# tick-display-mk-4.net
KiCad netlist of a schematic drawn in EAGLE
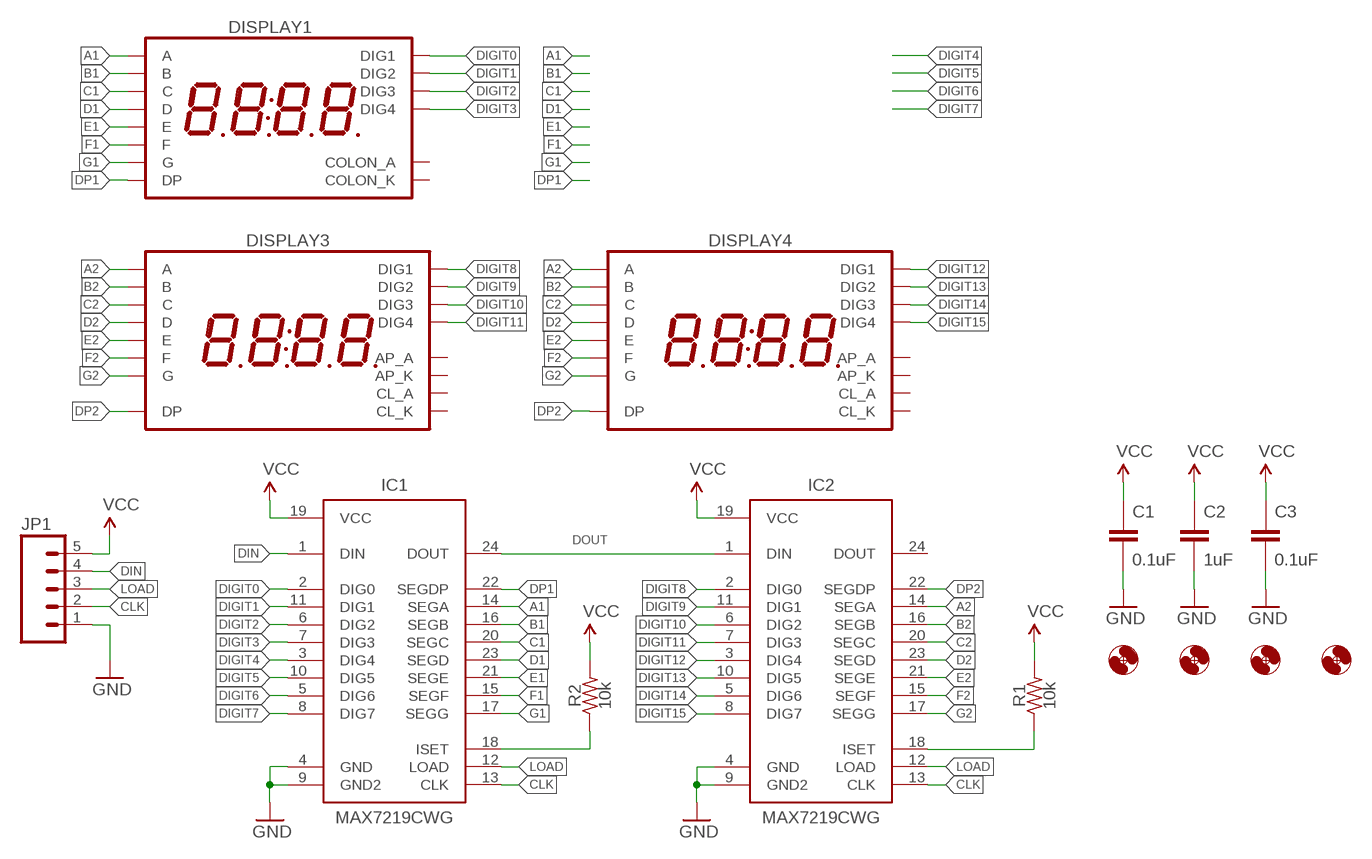
[diagram p0: schematic, sheet 1]

(export (version "E")
  (design (tool "Eeschema 10.0.6"))
  (components
    (comp (ref "C1")
      (value "0.1uF")
      (footprint "eagle-import:C025-024X044")
      (libsource (lib "eagle-import") (part "CAPACITOR-CERAMIC025-024X044"))
    )
    (comp (ref "C2")
      (value "1uF")
      (footprint "eagle-import:C025-024X044")
      (libsource (lib "eagle-import") (part "CAPACITOR-CERAMIC025-024X044"))
    )
    (comp (ref "C3")
      (value "0.1uF")
      (footprint "eagle-import:C025-024X044")
      (libsource (lib "eagle-import") (part "CAPACITOR-CERAMIC025-024X044"))
    )
    (comp (ref "DISPLAY1")
      (value "7SEG_4DIGIT_COLON14.2MM-CC")
      (footprint "eagle-import:7SEG_4DIG_0.56IN_14MM_ADAFRUIT")
      (libsource (lib "eagle-import") (part "7SEG_4DIGIT_COLON14.2MM-CC"))
    )
    (comp (ref "DISPLAY3")
      (value "7SEG_4DIGIT_COLON_APOS")
      (footprint "eagle-import:7SEG_4DIG_10MM")
      (libsource (lib "eagle-import") (part "7SEG_4DIGIT_COLON_APOS"))
    )
    (comp (ref "DISPLAY4")
      (value "7SEG_4DIGIT_COLON_APOS")
      (footprint "eagle-import:7SEG_4DIG_10MM")
      (libsource (lib "eagle-import") (part "7SEG_4DIGIT_COLON_APOS"))
    )
    (comp (ref "H1")
      (value "HOLE#2")
      (footprint "eagle-import:HOLE-#2")
      (libsource (lib "eagle-import") (part "HOLE#2"))
    )
    (comp (ref "H2")
      (value "HOLE#2")
      (footprint "eagle-import:HOLE-#2")
      (libsource (lib "eagle-import") (part "HOLE#2"))
    )
    (comp (ref "H3")
      (value "HOLE#2")
      (footprint "eagle-import:HOLE-#2")
      (libsource (lib "eagle-import") (part "HOLE#2"))
    )
    (comp (ref "H4")
      (value "HOLE#2")
      (footprint "eagle-import:HOLE-#2")
      (libsource (lib "eagle-import") (part "HOLE#2"))
    )
    (comp (ref "IC1")
      (value "MAX7219CWG")
      (footprint "eagle-import:SO24W")
      (libsource (lib "eagle-import") (part "MAX7219SOIC-W"))
    )
    (comp (ref "IC2")
      (value "MAX7219CWG")
      (footprint "eagle-import:SO24W")
      (libsource (lib "eagle-import") (part "MAX7219SOIC-W"))
    )
    (comp (ref "JP1")
      (value "M05JST-PH-VERT-PTH")
      (footprint "eagle-import:JST-5-PH-VERT-PTH")
      (libsource (lib "eagle-import") (part "M05JST-PH-VERT-PTH"))
    )
    (comp (ref "R1")
      (value "10k")
      (footprint "eagle-import:RESISTOR-AXIAL-PTH-5.08MM")
      (libsource (lib "eagle-import") (part "RESISTORPTH-AXIAL-5.08MM"))
    )
    (comp (ref "R2")
      (value "10k")
      (footprint "eagle-import:RESISTOR-AXIAL-PTH-5.08MM")
      (libsource (lib "eagle-import") (part "RESISTORPTH-AXIAL-5.08MM"))
    )
  )
  (nets
    (net (code "1") (name "/DOUT") (class "Default")
      (node (ref "IC1") (pin "24") (pinfunction "DOUT_24") (pintype "bidirectional"))
      (node (ref "IC2") (pin "1") (pinfunction "DIN_1") (pintype "bidirectional"))
    )
    (net (code "2") (name "A1") (class "Default")
      (node (ref "DISPLAY1") (pin "P$13") (pinfunction "A_P$13") (pintype "passive"))
      (node (ref "IC1") (pin "14") (pinfunction "SEGA_14") (pintype "bidirectional"))
    )
    (net (code "3") (name "A2") (class "Default")
      (node (ref "DISPLAY3") (pin "14") (pinfunction "A_14") (pintype "passive"))
      (node (ref "DISPLAY4") (pin "14") (pinfunction "A_14") (pintype "passive"))
      (node (ref "IC2") (pin "14") (pinfunction "SEGA_14") (pintype "bidirectional"))
    )
    (net (code "4") (name "B1") (class "Default")
      (node (ref "DISPLAY1") (pin "P$9") (pinfunction "B_P$9") (pintype "passive"))
      (node (ref "IC1") (pin "16") (pinfunction "SEGB_16") (pintype "bidirectional"))
    )
    (net (code "5") (name "B2") (class "Default")
      (node (ref "DISPLAY3") (pin "16") (pinfunction "B_16") (pintype "passive"))
      (node (ref "DISPLAY4") (pin "16") (pinfunction "B_16") (pintype "passive"))
      (node (ref "IC2") (pin "16") (pinfunction "SEGB_16") (pintype "bidirectional"))
    )
    (net (code "6") (name "C1") (class "Default")
      (node (ref "DISPLAY1") (pin "P$4") (pinfunction "C_P$4") (pintype "passive"))
      (node (ref "IC1") (pin "20") (pinfunction "SEGC_20") (pintype "bidirectional"))
    )
    (net (code "7") (name "C2") (class "Default")
      (node (ref "DISPLAY3") (pin "13") (pinfunction "C_13") (pintype "passive"))
      (node (ref "DISPLAY4") (pin "13") (pinfunction "C_13") (pintype "passive"))
      (node (ref "IC2") (pin "20") (pinfunction "SEGC_20") (pintype "bidirectional"))
    )
    (net (code "8") (name "CLK") (class "Default")
      (node (ref "IC1") (pin "13") (pinfunction "CLK_13") (pintype "bidirectional"))
      (node (ref "IC2") (pin "13") (pinfunction "CLK_13") (pintype "bidirectional"))
      (node (ref "JP1") (pin "2") (pinfunction "2_2") (pintype "passive"))
    )
    (net (code "9") (name "D1") (class "Default")
      (node (ref "DISPLAY1") (pin "P$2") (pinfunction "D_P$2") (pintype "passive"))
      (node (ref "IC1") (pin "23") (pinfunction "SEGD_23") (pintype "bidirectional"))
    )
    (net (code "10") (name "D2") (class "Default")
      (node (ref "DISPLAY3") (pin "3") (pinfunction "D_3") (pintype "passive"))
      (node (ref "DISPLAY4") (pin "3") (pinfunction "D_3") (pintype "passive"))
      (node (ref "IC2") (pin "23") (pinfunction "SEGD_23") (pintype "bidirectional"))
    )
    (net (code "11") (name "DIGIT0") (class "Default")
      (node (ref "DISPLAY1") (pin "P$14") (pinfunction "DIG1_P$14") (pintype "passive"))
      (node (ref "IC1") (pin "2") (pinfunction "DIG0_2") (pintype "bidirectional"))
    )
    (net (code "12") (name "DIGIT1") (class "Default")
      (node (ref "DISPLAY1") (pin "P$11") (pinfunction "DIG2_P$11") (pintype "passive"))
      (node (ref "IC1") (pin "11") (pinfunction "DIG1_11") (pintype "bidirectional"))
    )
    (net (code "13") (name "DIGIT2") (class "Default")
      (node (ref "DISPLAY1") (pin "P$10") (pinfunction "DIG3_P$10") (pintype "passive"))
      (node (ref "IC1") (pin "6") (pinfunction "DIG2_6") (pintype "bidirectional"))
    )
    (net (code "14") (name "DIGIT3") (class "Default")
      (node (ref "DISPLAY1") (pin "P$6") (pinfunction "DIG4_P$6") (pintype "passive"))
      (node (ref "IC1") (pin "7") (pinfunction "DIG3_7") (pintype "bidirectional"))
    )
    (net (code "15") (name "DIGIT4") (class "Default")
      (node (ref "IC1") (pin "3") (pinfunction "DIG4_3") (pintype "bidirectional"))
    )
    (net (code "16") (name "DIGIT5") (class "Default")
      (node (ref "IC1") (pin "10") (pinfunction "DIG5_10") (pintype "bidirectional"))
    )
    (net (code "17") (name "DIGIT6") (class "Default")
      (node (ref "IC1") (pin "5") (pinfunction "DIG6_5") (pintype "bidirectional"))
    )
    (net (code "18") (name "DIGIT7") (class "Default")
      (node (ref "IC1") (pin "8") (pinfunction "DIG7_8") (pintype "bidirectional"))
    )
    (net (code "19") (name "DIGIT8") (class "Default")
      (node (ref "DISPLAY3") (pin "1") (pinfunction "DIG1_1") (pintype "passive"))
      (node (ref "IC2") (pin "2") (pinfunction "DIG0_2") (pintype "bidirectional"))
    )
    (net (code "20") (name "DIGIT9") (class "Default")
      (node (ref "DISPLAY3") (pin "2") (pinfunction "DIG2_2") (pintype "passive"))
      (node (ref "IC2") (pin "11") (pinfunction "DIG1_11") (pintype "bidirectional"))
    )
    (net (code "21") (name "DIGIT10") (class "Default")
      (node (ref "DISPLAY3") (pin "6") (pinfunction "DIG3_6") (pintype "passive"))
      (node (ref "IC2") (pin "6") (pinfunction "DIG2_6") (pintype "bidirectional"))
    )
    (net (code "22") (name "DIGIT11") (class "Default")
      (node (ref "DISPLAY3") (pin "8") (pinfunction "DIG4_8") (pintype "passive"))
      (node (ref "IC2") (pin "7") (pinfunction "DIG3_7") (pintype "bidirectional"))
    )
    (net (code "23") (name "DIGIT12") (class "Default")
      (node (ref "DISPLAY4") (pin "1") (pinfunction "DIG1_1") (pintype "passive"))
      (node (ref "IC2") (pin "3") (pinfunction "DIG4_3") (pintype "bidirectional"))
    )
    (net (code "24") (name "DIGIT13") (class "Default")
      (node (ref "DISPLAY4") (pin "2") (pinfunction "DIG2_2") (pintype "passive"))
      (node (ref "IC2") (pin "10") (pinfunction "DIG5_10") (pintype "bidirectional"))
    )
    (net (code "25") (name "DIGIT14") (class "Default")
      (node (ref "DISPLAY4") (pin "6") (pinfunction "DIG3_6") (pintype "passive"))
      (node (ref "IC2") (pin "5") (pinfunction "DIG6_5") (pintype "bidirectional"))
    )
    (net (code "26") (name "DIGIT15") (class "Default")
      (node (ref "DISPLAY4") (pin "8") (pinfunction "DIG4_8") (pintype "passive"))
      (node (ref "IC2") (pin "8") (pinfunction "DIG7_8") (pintype "bidirectional"))
    )
    (net (code "27") (name "DIN") (class "Default")
      (node (ref "IC1") (pin "1") (pinfunction "DIN_1") (pintype "bidirectional"))
      (node (ref "JP1") (pin "4") (pinfunction "4_4") (pintype "passive"))
    )
    (net (code "28") (name "DP1") (class "Default")
      (node (ref "DISPLAY1") (pin "P$3") (pinfunction "DP_P$3") (pintype "passive"))
      (node (ref "IC1") (pin "22") (pinfunction "SEGDP_22") (pintype "bidirectional"))
    )
    (net (code "29") (name "DP2") (class "Default")
      (node (ref "DISPLAY3") (pin "7") (pinfunction "DP_7") (pintype "passive"))
      (node (ref "DISPLAY4") (pin "7") (pinfunction "DP_7") (pintype "passive"))
      (node (ref "IC2") (pin "22") (pinfunction "SEGDP_22") (pintype "bidirectional"))
    )
    (net (code "30") (name "E1") (class "Default")
      (node (ref "DISPLAY1") (pin "P$1") (pinfunction "E_P$1") (pintype "passive"))
      (node (ref "IC1") (pin "21") (pinfunction "SEGE_21") (pintype "bidirectional"))
    )
    (net (code "31") (name "E2") (class "Default")
      (node (ref "DISPLAY3") (pin "5") (pinfunction "E_5") (pintype "passive"))
      (node (ref "DISPLAY4") (pin "5") (pinfunction "E_5") (pintype "passive"))
      (node (ref "IC2") (pin "21") (pinfunction "SEGE_21") (pintype "bidirectional"))
    )
    (net (code "32") (name "F1") (class "Default")
      (node (ref "DISPLAY1") (pin "P$12") (pinfunction "F_P$12") (pintype "passive"))
      (node (ref "IC1") (pin "15") (pinfunction "SEGF_15") (pintype "bidirectional"))
    )
    (net (code "33") (name "F2") (class "Default")
      (node (ref "DISPLAY3") (pin "11") (pinfunction "F_11") (pintype "passive"))
      (node (ref "DISPLAY4") (pin "11") (pinfunction "F_11") (pintype "passive"))
      (node (ref "IC2") (pin "15") (pinfunction "SEGF_15") (pintype "bidirectional"))
    )
    (net (code "34") (name "G1") (class "Default")
      (node (ref "DISPLAY1") (pin "P$5") (pinfunction "G_P$5") (pintype "passive"))
      (node (ref "IC1") (pin "17") (pinfunction "SEGG_17") (pintype "bidirectional"))
    )
    (net (code "35") (name "G2") (class "Default")
      (node (ref "DISPLAY3") (pin "15") (pinfunction "G_15") (pintype "passive"))
      (node (ref "DISPLAY4") (pin "15") (pinfunction "G_15") (pintype "passive"))
      (node (ref "IC2") (pin "17") (pinfunction "SEGG_17") (pintype "bidirectional"))
    )
    (net (code "36") (name "GND") (class "Default")
      (node (ref "C1") (pin "2") (pinfunction "2_2") (pintype "passive"))
      (node (ref "C2") (pin "2") (pinfunction "2_2") (pintype "passive"))
      (node (ref "C3") (pin "2") (pinfunction "2_2") (pintype "passive"))
      (node (ref "IC1") (pin "4") (pinfunction "GND_4") (pintype "bidirectional"))
      (node (ref "IC1") (pin "9") (pinfunction "GND2_9") (pintype "bidirectional"))
      (node (ref "IC2") (pin "4") (pinfunction "GND_4") (pintype "bidirectional"))
      (node (ref "IC2") (pin "9") (pinfunction "GND2_9") (pintype "bidirectional"))
      (node (ref "JP1") (pin "1") (pinfunction "1_1") (pintype "passive"))
    )
    (net (code "37") (name "LOAD") (class "Default")
      (node (ref "IC1") (pin "12") (pinfunction "LOAD_12") (pintype "bidirectional"))
      (node (ref "IC2") (pin "12") (pinfunction "LOAD_12") (pintype "bidirectional"))
      (node (ref "JP1") (pin "3") (pinfunction "3_3") (pintype "passive"))
    )
    (net (code "38") (name "Net-(IC1-ISET)") (class "Default")
      (node (ref "IC1") (pin "18") (pinfunction "ISET_18") (pintype "bidirectional"))
      (node (ref "R2") (pin "P$1") (pinfunction "1_P$1") (pintype "passive"))
    )
    (net (code "39") (name "Net-(IC2-ISET)") (class "Default")
      (node (ref "IC2") (pin "18") (pinfunction "ISET_18") (pintype "bidirectional"))
      (node (ref "R1") (pin "P$1") (pinfunction "1_P$1") (pintype "passive"))
    )
    (net (code "40") (name "VCC") (class "Default")
      (node (ref "C1") (pin "1") (pinfunction "1_1") (pintype "passive"))
      (node (ref "C2") (pin "1") (pinfunction "1_1") (pintype "passive"))
      (node (ref "C3") (pin "1") (pinfunction "1_1") (pintype "passive"))
      (node (ref "IC1") (pin "19") (pinfunction "VCC_19") (pintype "bidirectional"))
      (node (ref "IC2") (pin "19") (pinfunction "VCC_19") (pintype "bidirectional"))
      (node (ref "JP1") (pin "5") (pinfunction "5_5") (pintype "passive"))
      (node (ref "R1") (pin "P$2") (pinfunction "2_P$2") (pintype "passive"))
      (node (ref "R2") (pin "P$2") (pinfunction "2_P$2") (pintype "passive"))
    )
    (net (code "41") (name "unconnected-(DISPLAY1-COLON_A-PadP$8)") (class "Default")
      (node (ref "DISPLAY1") (pin "P$8") (pinfunction "COLON_A_P$8") (pintype "passive"))
    )
    (net (code "42") (name "unconnected-(DISPLAY1-COLON_K-PadP$7)") (class "Default")
      (node (ref "DISPLAY1") (pin "P$7") (pinfunction "COLON_K_P$7") (pintype "passive"))
    )
    (net (code "43") (name "unconnected-(DISPLAY3-AP_A-Pad10)") (class "Default")
      (node (ref "DISPLAY3") (pin "10") (pinfunction "AP_A_10") (pintype "bidirectional"))
    )
    (net (code "44") (name "unconnected-(DISPLAY3-AP_K-Pad9)") (class "Default")
      (node (ref "DISPLAY3") (pin "9") (pinfunction "AP_K_9") (pintype "bidirectional"))
    )
    (net (code "45") (name "unconnected-(DISPLAY3-CL_A-Pad4)") (class "Default")
      (node (ref "DISPLAY3") (pin "4") (pinfunction "CL_A_4") (pintype "passive"))
    )
    (net (code "46") (name "unconnected-(DISPLAY3-CL_K-Pad12)") (class "Default")
      (node (ref "DISPLAY3") (pin "12") (pinfunction "CL_K_12") (pintype "passive"))
    )
    (net (code "47") (name "unconnected-(DISPLAY4-AP_A-Pad10)") (class "Default")
      (node (ref "DISPLAY4") (pin "10") (pinfunction "AP_A_10") (pintype "bidirectional"))
    )
    (net (code "48") (name "unconnected-(DISPLAY4-AP_K-Pad9)") (class "Default")
      (node (ref "DISPLAY4") (pin "9") (pinfunction "AP_K_9") (pintype "bidirectional"))
    )
    (net (code "49") (name "unconnected-(DISPLAY4-CL_A-Pad4)") (class "Default")
      (node (ref "DISPLAY4") (pin "4") (pinfunction "CL_A_4") (pintype "passive"))
    )
    (net (code "50") (name "unconnected-(DISPLAY4-CL_K-Pad12)") (class "Default")
      (node (ref "DISPLAY4") (pin "12") (pinfunction "CL_K_12") (pintype "passive"))
    )
    (net (code "51") (name "unconnected-(IC2-DOUT-Pad24)") (class "Default")
      (node (ref "IC2") (pin "24") (pinfunction "DOUT_24") (pintype "bidirectional"))
    )
  )
)
